# LCD_board.net
KiCad netlist of a schematic drawn in EAGLE
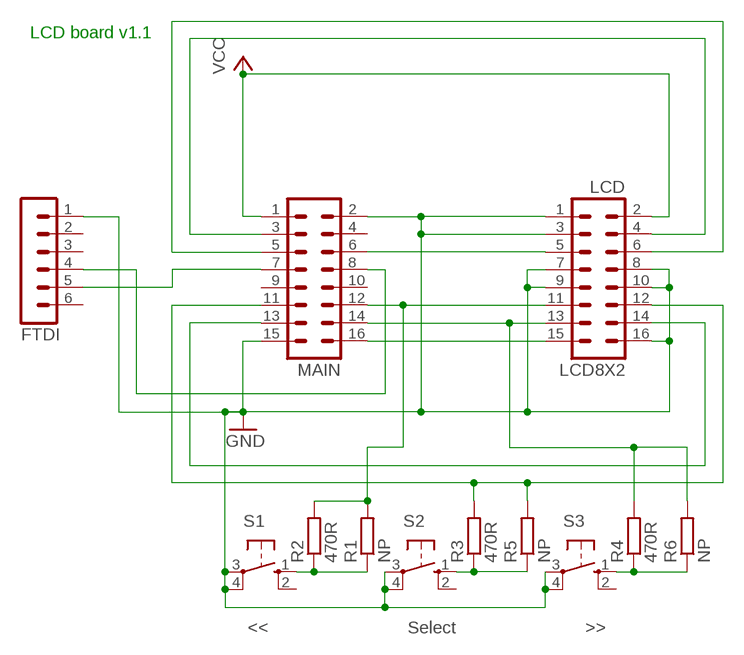
[diagram p0: schematic, sheet 1]

(export (version "E")
  (design (tool "Eeschema 10.0.6"))
  (components
    (comp (ref "FTDI")
      (value "MA06-1")
      (footprint "eagle-import:MA06-1")
      (libsource (lib "eagle-import") (part "MA06-1"))
    )
    (comp (ref "LCD8X2")
      (value "LCD")
      (footprint "eagle-import:MA08-2")
      (libsource (lib "eagle-import") (part "MA08-2"))
    )
    (comp (ref "MAIN")
      (value "MA08-2")
      (footprint "eagle-import:MA08-2")
      (libsource (lib "eagle-import") (part "MA08-2"))
    )
    (comp (ref "R1")
      (value "NP")
      (footprint "eagle-import:0204_7")
      (libsource (lib "eagle-import") (part "R-EU_0204/7"))
    )
    (comp (ref "R2")
      (value "470R")
      (footprint "eagle-import:R0805")
      (libsource (lib "eagle-import") (part "R-EU_R0805"))
    )
    (comp (ref "R3")
      (value "470R")
      (footprint "eagle-import:R0805")
      (libsource (lib "eagle-import") (part "R-EU_R0805"))
    )
    (comp (ref "R4")
      (value "470R")
      (footprint "eagle-import:R0805")
      (libsource (lib "eagle-import") (part "R-EU_R0805"))
    )
    (comp (ref "R5")
      (value "NP")
      (footprint "eagle-import:0204_7")
      (libsource (lib "eagle-import") (part "R-EU_0204/7"))
    )
    (comp (ref "R6")
      (value "NP")
      (footprint "eagle-import:0204_7")
      (libsource (lib "eagle-import") (part "R-EU_0204/7"))
    )
    (comp (ref "S1")
      (value "<<")
      (footprint "eagle-import:B3F-10XX")
      (fields (field (name "MPN") "B3F-1000"))
      (libsource (lib "eagle-import") (part "10-XX"))
    )
    (comp (ref "S2")
      (value "Select")
      (footprint "eagle-import:B3F-10XX")
      (fields (field (name "MPN") "B3F-1000"))
      (libsource (lib "eagle-import") (part "10-XX"))
    )
    (comp (ref "S3")
      (value ">>")
      (footprint "eagle-import:B3F-10XX")
      (fields (field (name "MPN") "B3F-1000"))
      (libsource (lib "eagle-import") (part "10-XX"))
    )
  )
  (nets
    (net (code "1") (name "GND") (class "Default")
      (node (ref "FTDI") (pin "1") (pinfunction "1_1") (pintype "passive"))
      (node (ref "LCD8X2") (pin "1") (pinfunction "1_1") (pintype "passive"))
      (node (ref "LCD8X2") (pin "10") (pinfunction "10_10") (pintype "passive"))
      (node (ref "LCD8X2") (pin "16") (pinfunction "16_16") (pintype "passive"))
      (node (ref "LCD8X2") (pin "3") (pinfunction "3_3") (pintype "passive"))
      (node (ref "LCD8X2") (pin "7") (pinfunction "7_7") (pintype "passive"))
      (node (ref "LCD8X2") (pin "8") (pinfunction "8_8") (pintype "passive"))
      (node (ref "LCD8X2") (pin "9") (pinfunction "9_9") (pintype "passive"))
      (node (ref "MAIN") (pin "15") (pinfunction "15_15") (pintype "passive"))
      (node (ref "MAIN") (pin "2") (pinfunction "2_2") (pintype "passive"))
      (node (ref "S1") (pin "3") (pinfunction "P_3") (pintype "passive"))
      (node (ref "S1") (pin "4") (pinfunction "P1_4") (pintype "passive"))
      (node (ref "S2") (pin "3") (pinfunction "P_3") (pintype "passive"))
      (node (ref "S2") (pin "4") (pinfunction "P1_4") (pintype "passive"))
      (node (ref "S3") (pin "3") (pinfunction "P_3") (pintype "passive"))
      (node (ref "S3") (pin "4") (pinfunction "P1_4") (pintype "passive"))
    )
    (net (code "2") (name "Net-(FTDI-Pad4)") (class "Default")
      (node (ref "FTDI") (pin "4") (pinfunction "4_4") (pintype "passive"))
      (node (ref "MAIN") (pin "8") (pinfunction "8_8") (pintype "passive"))
    )
    (net (code "3") (name "Net-(FTDI-Pad5)") (class "Default")
      (node (ref "FTDI") (pin "5") (pinfunction "5_5") (pintype "passive"))
      (node (ref "MAIN") (pin "7") (pinfunction "7_7") (pintype "passive"))
    )
    (net (code "4") (name "Net-(LCD8X2-Pad4)") (class "Default")
      (node (ref "LCD8X2") (pin "4") (pinfunction "4_4") (pintype "passive"))
      (node (ref "MAIN") (pin "3") (pinfunction "3_3") (pintype "passive"))
    )
    (net (code "5") (name "Net-(LCD8X2-Pad5)") (class "Default")
      (node (ref "LCD8X2") (pin "5") (pinfunction "5_5") (pintype "passive"))
      (node (ref "MAIN") (pin "6") (pinfunction "6_6") (pintype "passive"))
    )
    (net (code "6") (name "Net-(LCD8X2-Pad6)") (class "Default")
      (node (ref "LCD8X2") (pin "6") (pinfunction "6_6") (pintype "passive"))
      (node (ref "MAIN") (pin "5") (pinfunction "5_5") (pintype "passive"))
    )
    (net (code "7") (name "Net-(LCD8X2-Pad11)") (class "Default")
      (node (ref "LCD8X2") (pin "11") (pinfunction "11_11") (pintype "passive"))
      (node (ref "MAIN") (pin "12") (pinfunction "12_12") (pintype "passive"))
      (node (ref "R1") (pin "2") (pinfunction "2_2") (pintype "passive"))
      (node (ref "R2") (pin "2") (pinfunction "2_2") (pintype "passive"))
    )
    (net (code "8") (name "Net-(LCD8X2-Pad12)") (class "Default")
      (node (ref "LCD8X2") (pin "12") (pinfunction "12_12") (pintype "passive"))
      (node (ref "MAIN") (pin "11") (pinfunction "11_11") (pintype "passive"))
      (node (ref "R3") (pin "2") (pinfunction "2_2") (pintype "passive"))
      (node (ref "R5") (pin "2") (pinfunction "2_2") (pintype "passive"))
    )
    (net (code "9") (name "Net-(LCD8X2-Pad13)") (class "Default")
      (node (ref "LCD8X2") (pin "13") (pinfunction "13_13") (pintype "passive"))
      (node (ref "MAIN") (pin "14") (pinfunction "14_14") (pintype "passive"))
      (node (ref "R4") (pin "2") (pinfunction "2_2") (pintype "passive"))
      (node (ref "R6") (pin "2") (pinfunction "2_2") (pintype "passive"))
    )
    (net (code "10") (name "Net-(LCD8X2-Pad14)") (class "Default")
      (node (ref "LCD8X2") (pin "14") (pinfunction "14_14") (pintype "passive"))
      (node (ref "MAIN") (pin "13") (pinfunction "13_13") (pintype "passive"))
    )
    (net (code "11") (name "Net-(LCD8X2-Pad15)") (class "Default")
      (node (ref "LCD8X2") (pin "15") (pinfunction "15_15") (pintype "passive"))
      (node (ref "MAIN") (pin "16") (pinfunction "16_16") (pintype "passive"))
    )
    (net (code "12") (name "Net-(S1-S)") (class "Default")
      (node (ref "R1") (pin "1") (pinfunction "1_1") (pintype "passive"))
      (node (ref "R2") (pin "1") (pinfunction "1_1") (pintype "passive"))
      (node (ref "S1") (pin "1") (pinfunction "S_1") (pintype "passive"))
    )
    (net (code "13") (name "Net-(S2-S)") (class "Default")
      (node (ref "R3") (pin "1") (pinfunction "1_1") (pintype "passive"))
      (node (ref "R5") (pin "1") (pinfunction "1_1") (pintype "passive"))
      (node (ref "S2") (pin "1") (pinfunction "S_1") (pintype "passive"))
    )
    (net (code "14") (name "Net-(S3-S)") (class "Default")
      (node (ref "R4") (pin "1") (pinfunction "1_1") (pintype "passive"))
      (node (ref "R6") (pin "1") (pinfunction "1_1") (pintype "passive"))
      (node (ref "S3") (pin "1") (pinfunction "S_1") (pintype "passive"))
    )
    (net (code "15") (name "VCC") (class "Default")
      (node (ref "LCD8X2") (pin "2") (pinfunction "2_2") (pintype "passive"))
      (node (ref "MAIN") (pin "1") (pinfunction "1_1") (pintype "passive"))
    )
    (net (code "16") (name "unconnected-(FTDI-Pad2)") (class "Default")
      (node (ref "FTDI") (pin "2") (pinfunction "2_2") (pintype "passive"))
    )
    (net (code "17") (name "unconnected-(FTDI-Pad3)") (class "Default")
      (node (ref "FTDI") (pin "3") (pinfunction "3_3") (pintype "passive"))
    )
    (net (code "18") (name "unconnected-(FTDI-Pad6)") (class "Default")
      (node (ref "FTDI") (pin "6") (pinfunction "6_6") (pintype "passive"))
    )
    (net (code "19") (name "unconnected-(MAIN-Pad4)") (class "Default")
      (node (ref "MAIN") (pin "4") (pinfunction "4_4") (pintype "passive"))
    )
    (net (code "20") (name "unconnected-(MAIN-Pad9)") (class "Default")
      (node (ref "MAIN") (pin "9") (pinfunction "9_9") (pintype "passive"))
    )
    (net (code "21") (name "unconnected-(MAIN-Pad10)") (class "Default")
      (node (ref "MAIN") (pin "10") (pinfunction "10_10") (pintype "passive"))
    )
    (net (code "22") (name "unconnected-(S1-S1-Pad2)") (class "Default")
      (node (ref "S1") (pin "2") (pinfunction "S1_2") (pintype "passive"))
    )
    (net (code "23") (name "unconnected-(S2-S1-Pad2)") (class "Default")
      (node (ref "S2") (pin "2") (pinfunction "S1_2") (pintype "passive"))
    )
    (net (code "24") (name "unconnected-(S3-S1-Pad2)") (class "Default")
      (node (ref "S3") (pin "2") (pinfunction "S1_2") (pintype "passive"))
    )
  )
)
